# Anahtarlamasemasi.net
KiCad netlist of a schematic drawn in Altium Designer
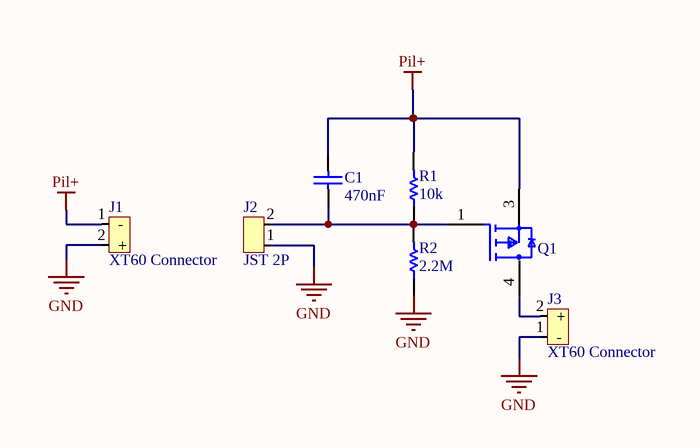
[diagram p0: Anahtarlamasemasi.SchDoc]

(export (version "E")
  (design (tool "Eeschema 10.0.6"))
  (components
    (comp (ref "C1")
      (value "470nF")
      (footprint "CAP0805")
      (description "Capacitor")
      (fields (field (name "Comment") "Cap") (field (name "PUBLISHER") "Altium Limited"))
      (libsource (lib "Miscellaneous Devices") (part "Cap"))
    )
    (comp (ref "J1") (value "XT60 Connector") (footprint "XT60_H") (libsource (lib "") (part "XT60_1")))
    (comp (ref "J2") (value "JST 2P") (footprint "JST_Horizontal") (libsource (lib "Schlib3") (part "JST")))
    (comp (ref "J3") (value "XT60 Connector") (footprint "XT60_H") (libsource (lib "Schlib3") (part "XT60")))
    (comp (ref "Q1")
      (value "SUD50P04-08-GE3")
      (footprint "Vishay_T16-0236_MFG")
      (libsource (lib "Schlib3") (part "SUD50P04-08-GE3"))
    )
    (comp (ref "R1")
      (value "10k")
      (footprint "RES0805")
      (description "Resistor")
      (fields (field (name "Comment") "Res1") (field (name "PUBLISHER") "Altium Limited"))
      (libsource (lib "Miscellaneous Devices") (part "Res1"))
    )
    (comp (ref "R2")
      (value "2.2M")
      (footprint "RES0805")
      (description "Resistor")
      (fields (field (name "Comment") "Res1") (field (name "PUBLISHER") "Altium Limited"))
      (libsource (lib "Miscellaneous Devices") (part "Res1"))
    )
  )
  (nets
    (net (code "1") (name "GND") (class "Default")
      (node (ref "J1") (pin "2") (pinfunction "+_2") (pintype "passive"))
      (node (ref "J2") (pin "1") (pinfunction "1_1") (pintype "passive"))
      (node (ref "J3") (pin "1") (pinfunction "-_1") (pintype "passive"))
      (node (ref "R2") (pin "1") (pinfunction "1_1") (pintype "passive"))
    )
    (net (code "2") (name "Net-(J3-+)") (class "Default")
      (node (ref "J3") (pin "2") (pinfunction "+_2") (pintype "passive"))
      (node (ref "Q1") (pin "4") (pinfunction "D_4") (pintype "passive"))
    )
    (net (code "3") (name "Net-(Q1-G)") (class "Default")
      (node (ref "C1") (pin "1") (pinfunction "1_1") (pintype "passive"))
      (node (ref "J2") (pin "2") (pinfunction "2_2") (pintype "passive"))
      (node (ref "Q1") (pin "1") (pinfunction "G_1") (pintype "passive"))
      (node (ref "R1") (pin "1") (pinfunction "1_1") (pintype "passive"))
      (node (ref "R2") (pin "2") (pinfunction "2_2") (pintype "passive"))
    )
    (net (code "4") (name "Pil+") (class "Default")
      (node (ref "C1") (pin "2") (pinfunction "2_2") (pintype "passive"))
      (node (ref "J1") (pin "1") (pinfunction "-_1") (pintype "passive"))
      (node (ref "Q1") (pin "3") (pinfunction "S_3") (pintype "passive"))
      (node (ref "R1") (pin "2") (pinfunction "2_2") (pintype "passive"))
    )
  )
)
